# ATX80.net
KiCad netlist of a schematic drawn in EAGLE
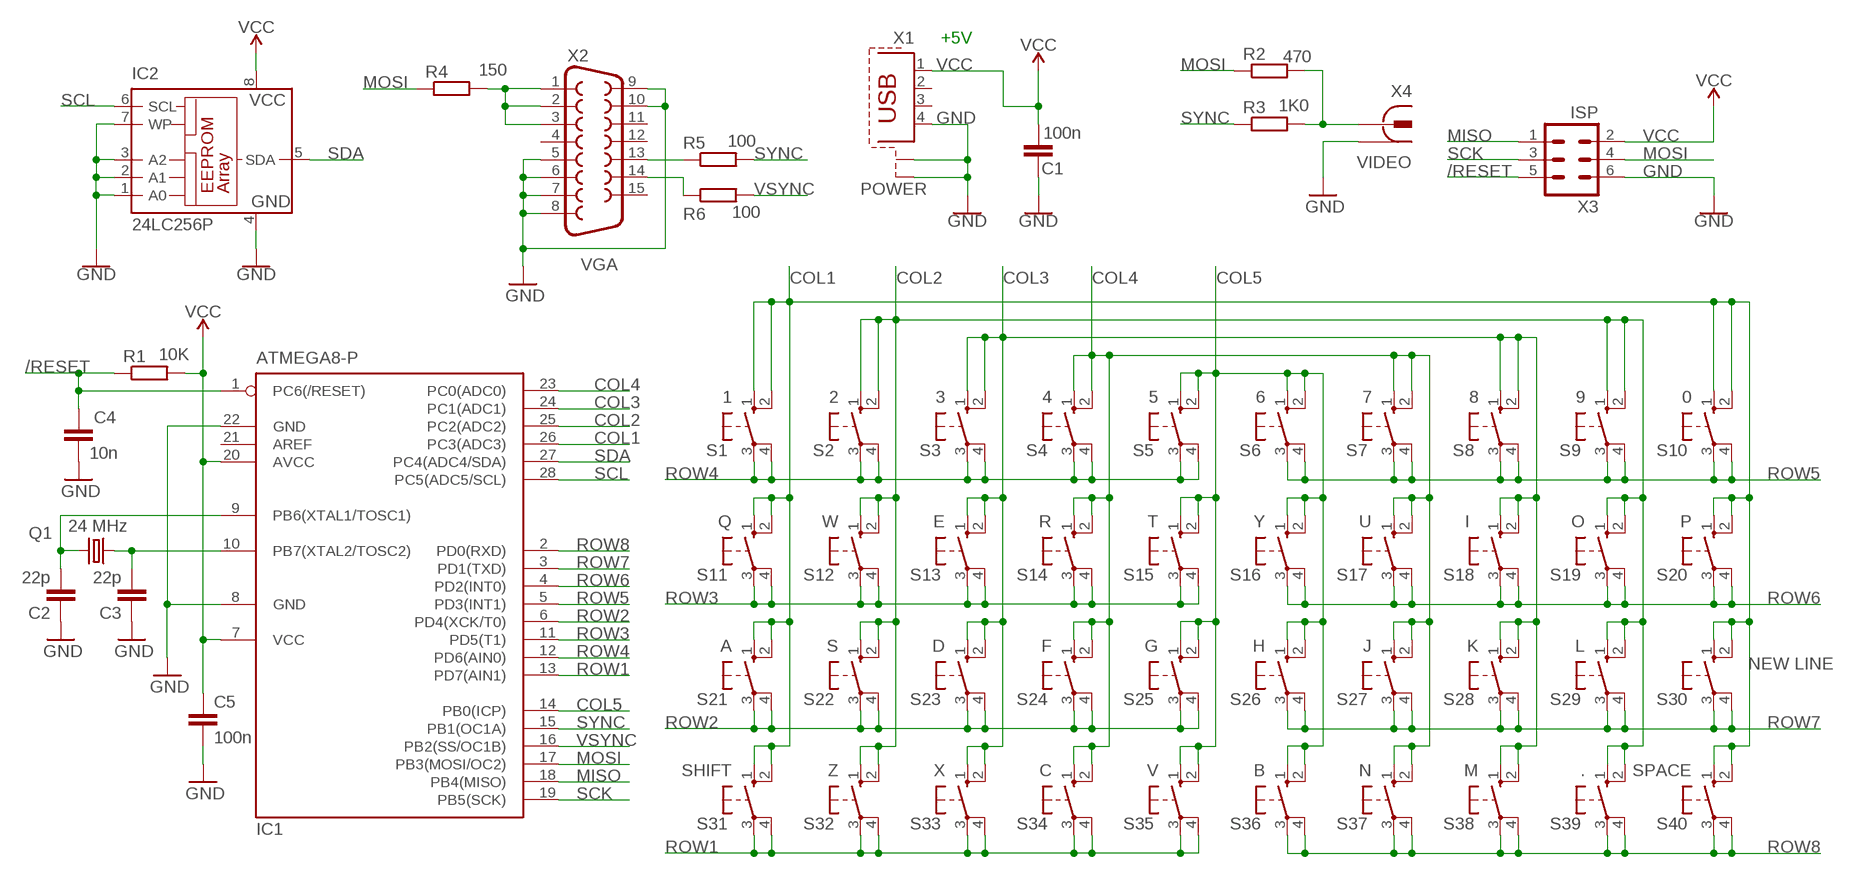
[diagram p0: schematic, sheet 1]

(export (version "E")
  (design (tool "Eeschema 10.0.6"))
  (components
    (comp (ref "C1")
      (value "100n")
      (footprint "eagle-import:C050-024X044")
      (libsource (lib "eagle-import") (part "C-EU050-024X044"))
    )
    (comp (ref "C2")
      (value "22p")
      (footprint "eagle-import:C050-024X044")
      (libsource (lib "eagle-import") (part "C-EU050-024X044"))
    )
    (comp (ref "C3")
      (value "22p")
      (footprint "eagle-import:C050-024X044")
      (libsource (lib "eagle-import") (part "C-EU050-024X044"))
    )
    (comp (ref "C4")
      (value "10n")
      (footprint "eagle-import:C050-024X044")
      (libsource (lib "eagle-import") (part "C-EU050-024X044"))
    )
    (comp (ref "C5")
      (value "100n")
      (footprint "eagle-import:C050-024X044")
      (libsource (lib "eagle-import") (part "C-EU050-024X044"))
    )
    (comp (ref "IC1")
      (value "ATMEGA8-P")
      (footprint "eagle-import:DIL28-3")
      (libsource (lib "eagle-import") (part "MEGA8-P"))
    )
    (comp (ref "IC2")
      (value "24LC256P")
      (footprint "eagle-import:DIL8")
      (fields (field (name "MF") "MICROCHIP") (field (name "MPN") "24LC256-E/P"))
      (libsource (lib "eagle-import") (part "24PLC256"))
    )
    (comp (ref "Q1")
      (value "24 MHz")
      (footprint "eagle-import:HC49U-V")
      (libsource (lib "eagle-import") (part "CRYSTALHC49U-V"))
    )
    (comp (ref "R1")
      (value "10K")
      (footprint "eagle-import:0204_7")
      (libsource (lib "eagle-import") (part "R-EU_0204/7"))
    )
    (comp (ref "R2")
      (value "470")
      (footprint "eagle-import:0204_7")
      (libsource (lib "eagle-import") (part "R-EU_0204/7"))
    )
    (comp (ref "R3")
      (value "1K0")
      (footprint "eagle-import:0204_7")
      (libsource (lib "eagle-import") (part "R-EU_0204/7"))
    )
    (comp (ref "R4")
      (value "150")
      (footprint "eagle-import:0204_7")
      (libsource (lib "eagle-import") (part "R-EU_0204/7"))
    )
    (comp (ref "R5")
      (value "100")
      (footprint "eagle-import:0204_7")
      (libsource (lib "eagle-import") (part "R-EU_0204/7"))
    )
    (comp (ref "R6")
      (value "100")
      (footprint "eagle-import:0204_7")
      (libsource (lib "eagle-import") (part "R-EU_0204/7"))
    )
    (comp (ref "S1")
      (value "1")
      (footprint "eagle-import:B3F-10XX")
      (fields (field (name "MPN") "B3F-1000"))
      (libsource (lib "eagle-import") (part "10-XX"))
    )
    (comp (ref "S2")
      (value "2")
      (footprint "eagle-import:B3F-10XX")
      (fields (field (name "MPN") "B3F-1000"))
      (libsource (lib "eagle-import") (part "10-XX"))
    )
    (comp (ref "S3")
      (value "3")
      (footprint "eagle-import:B3F-10XX")
      (fields (field (name "MPN") "B3F-1000"))
      (libsource (lib "eagle-import") (part "10-XX"))
    )
    (comp (ref "S4")
      (value "4")
      (footprint "eagle-import:B3F-10XX")
      (fields (field (name "MPN") "B3F-1000"))
      (libsource (lib "eagle-import") (part "10-XX"))
    )
    (comp (ref "S5")
      (value "5")
      (footprint "eagle-import:B3F-10XX")
      (fields (field (name "MPN") "B3F-1000"))
      (libsource (lib "eagle-import") (part "10-XX"))
    )
    (comp (ref "S6")
      (value "6")
      (footprint "eagle-import:B3F-10XX")
      (fields (field (name "MPN") "B3F-1000"))
      (libsource (lib "eagle-import") (part "10-XX"))
    )
    (comp (ref "S7")
      (value "7")
      (footprint "eagle-import:B3F-10XX")
      (fields (field (name "MPN") "B3F-1000"))
      (libsource (lib "eagle-import") (part "10-XX"))
    )
    (comp (ref "S8")
      (value "8")
      (footprint "eagle-import:B3F-10XX")
      (fields (field (name "MPN") "B3F-1000"))
      (libsource (lib "eagle-import") (part "10-XX"))
    )
    (comp (ref "S9")
      (value "9")
      (footprint "eagle-import:B3F-10XX")
      (fields (field (name "MPN") "B3F-1000"))
      (libsource (lib "eagle-import") (part "10-XX"))
    )
    (comp (ref "S10")
      (value "0")
      (footprint "eagle-import:B3F-10XX")
      (fields (field (name "MPN") "B3F-1000"))
      (libsource (lib "eagle-import") (part "10-XX"))
    )
    (comp (ref "S11")
      (value "Q")
      (footprint "eagle-import:B3F-10XX")
      (fields (field (name "MPN") "B3F-1000"))
      (libsource (lib "eagle-import") (part "10-XX"))
    )
    (comp (ref "S12")
      (value "W")
      (footprint "eagle-import:B3F-10XX")
      (fields (field (name "MPN") "B3F-1000"))
      (libsource (lib "eagle-import") (part "10-XX"))
    )
    (comp (ref "S13")
      (value "E")
      (footprint "eagle-import:B3F-10XX")
      (fields (field (name "MPN") "B3F-1000"))
      (libsource (lib "eagle-import") (part "10-XX"))
    )
    (comp (ref "S14")
      (value "R")
      (footprint "eagle-import:B3F-10XX")
      (fields (field (name "MPN") "B3F-1000"))
      (libsource (lib "eagle-import") (part "10-XX"))
    )
    (comp (ref "S15")
      (value "T")
      (footprint "eagle-import:B3F-10XX")
      (fields (field (name "MPN") "B3F-1000"))
      (libsource (lib "eagle-import") (part "10-XX"))
    )
    (comp (ref "S16")
      (value "Y")
      (footprint "eagle-import:B3F-10XX")
      (fields (field (name "MPN") "B3F-1000"))
      (libsource (lib "eagle-import") (part "10-XX"))
    )
    (comp (ref "S17")
      (value "U")
      (footprint "eagle-import:B3F-10XX")
      (fields (field (name "MPN") "B3F-1000"))
      (libsource (lib "eagle-import") (part "10-XX"))
    )
    (comp (ref "S18")
      (value "I")
      (footprint "eagle-import:B3F-10XX")
      (fields (field (name "MPN") "B3F-1000"))
      (libsource (lib "eagle-import") (part "10-XX"))
    )
    (comp (ref "S19")
      (value "O")
      (footprint "eagle-import:B3F-10XX")
      (fields (field (name "MPN") "B3F-1000"))
      (libsource (lib "eagle-import") (part "10-XX"))
    )
    (comp (ref "S20")
      (value "P")
      (footprint "eagle-import:B3F-10XX")
      (fields (field (name "MPN") "B3F-1000"))
      (libsource (lib "eagle-import") (part "10-XX"))
    )
    (comp (ref "S21")
      (value "A")
      (footprint "eagle-import:B3F-10XX")
      (fields (field (name "MPN") "B3F-1000"))
      (libsource (lib "eagle-import") (part "10-XX"))
    )
    (comp (ref "S22")
      (value "S")
      (footprint "eagle-import:B3F-10XX")
      (fields (field (name "MPN") "B3F-1000"))
      (libsource (lib "eagle-import") (part "10-XX"))
    )
    (comp (ref "S23")
      (value "D")
      (footprint "eagle-import:B3F-10XX")
      (fields (field (name "MPN") "B3F-1000"))
      (libsource (lib "eagle-import") (part "10-XX"))
    )
    (comp (ref "S24")
      (value "F")
      (footprint "eagle-import:B3F-10XX")
      (fields (field (name "MPN") "B3F-1000"))
      (libsource (lib "eagle-import") (part "10-XX"))
    )
    (comp (ref "S25")
      (value "G")
      (footprint "eagle-import:B3F-10XX")
      (fields (field (name "MPN") "B3F-1000"))
      (libsource (lib "eagle-import") (part "10-XX"))
    )
    (comp (ref "S26")
      (value "H")
      (footprint "eagle-import:B3F-10XX")
      (fields (field (name "MPN") "B3F-1000"))
      (libsource (lib "eagle-import") (part "10-XX"))
    )
    (comp (ref "S27")
      (value "J")
      (footprint "eagle-import:B3F-10XX")
      (fields (field (name "MPN") "B3F-1000"))
      (libsource (lib "eagle-import") (part "10-XX"))
    )
    (comp (ref "S28")
      (value "K")
      (footprint "eagle-import:B3F-10XX")
      (fields (field (name "MPN") "B3F-1000"))
      (libsource (lib "eagle-import") (part "10-XX"))
    )
    (comp (ref "S29")
      (value "L")
      (footprint "eagle-import:B3F-10XX")
      (fields (field (name "MPN") "B3F-1000"))
      (libsource (lib "eagle-import") (part "10-XX"))
    )
    (comp (ref "S30")
      (value "NEW LINE")
      (footprint "eagle-import:B3F-10XX")
      (fields (field (name "MPN") "B3F-1000"))
      (libsource (lib "eagle-import") (part "10-XX"))
    )
    (comp (ref "S31")
      (value "SHIFT")
      (footprint "eagle-import:B3F-10XX")
      (fields (field (name "MPN") "B3F-1000"))
      (libsource (lib "eagle-import") (part "10-XX"))
    )
    (comp (ref "S32")
      (value "Z")
      (footprint "eagle-import:B3F-10XX")
      (fields (field (name "MPN") "B3F-1000"))
      (libsource (lib "eagle-import") (part "10-XX"))
    )
    (comp (ref "S33")
      (value "X")
      (footprint "eagle-import:B3F-10XX")
      (fields (field (name "MPN") "B3F-1000"))
      (libsource (lib "eagle-import") (part "10-XX"))
    )
    (comp (ref "S34")
      (value "C")
      (footprint "eagle-import:B3F-10XX")
      (fields (field (name "MPN") "B3F-1000"))
      (libsource (lib "eagle-import") (part "10-XX"))
    )
    (comp (ref "S35")
      (value "V")
      (footprint "eagle-import:B3F-10XX")
      (fields (field (name "MPN") "B3F-1000"))
      (libsource (lib "eagle-import") (part "10-XX"))
    )
    (comp (ref "S36")
      (value "B")
      (footprint "eagle-import:B3F-10XX")
      (fields (field (name "MPN") "B3F-1000"))
      (libsource (lib "eagle-import") (part "10-XX"))
    )
    (comp (ref "S37")
      (value "N")
      (footprint "eagle-import:B3F-10XX")
      (fields (field (name "MPN") "B3F-1000"))
      (libsource (lib "eagle-import") (part "10-XX"))
    )
    (comp (ref "S38")
      (value "M")
      (footprint "eagle-import:B3F-10XX")
      (fields (field (name "MPN") "B3F-1000"))
      (libsource (lib "eagle-import") (part "10-XX"))
    )
    (comp (ref "S39")
      (value ".")
      (footprint "eagle-import:B3F-10XX")
      (fields (field (name "MPN") "B3F-1000"))
      (libsource (lib "eagle-import") (part "10-XX"))
    )
    (comp (ref "S40")
      (value "SPACE")
      (footprint "eagle-import:B3F-10XX")
      (fields (field (name "MPN") "B3F-1000"))
      (libsource (lib "eagle-import") (part "10-XX"))
    )
    (comp (ref "X1")
      (value "POWER")
      (footprint "eagle-import:PN61729-S")
      (libsource (lib "eagle-import") (part "PN61729-S"))
    )
    (comp (ref "X2")
      (value "VGA")
      (footprint "eagle-import:HDF15H")
      (libsource (lib "eagle-import") (part "F15HDH"))
    )
    (comp (ref "X3")
      (value "ISP")
      (footprint "eagle-import:ML6L")
      (libsource (lib "eagle-import") (part "ML6L"))
    )
    (comp (ref "X4")
      (value "VIDEO")
      (footprint "eagle-import:736880-49")
      (libsource (lib "eagle-import") (part "736880-49"))
    )
  )
  (nets
    (net (code "1") (name "/COL1") (class "Default")
      (node (ref "IC1") (pin "26") (pinfunction "PC3(ADC3)_26") (pintype "bidirectional"))
      (node (ref "S1") (pin "1") (pinfunction "S_1") (pintype "passive"))
      (node (ref "S1") (pin "2") (pinfunction "S1_2") (pintype "passive"))
      (node (ref "S10") (pin "1") (pinfunction "S_1") (pintype "passive"))
      (node (ref "S10") (pin "2") (pinfunction "S1_2") (pintype "passive"))
      (node (ref "S11") (pin "1") (pinfunction "S_1") (pintype "passive"))
      (node (ref "S11") (pin "2") (pinfunction "S1_2") (pintype "passive"))
      (node (ref "S20") (pin "1") (pinfunction "S_1") (pintype "passive"))
      (node (ref "S20") (pin "2") (pinfunction "S1_2") (pintype "passive"))
      (node (ref "S21") (pin "1") (pinfunction "S_1") (pintype "passive"))
      (node (ref "S21") (pin "2") (pinfunction "S1_2") (pintype "passive"))
      (node (ref "S30") (pin "1") (pinfunction "S_1") (pintype "passive"))
      (node (ref "S30") (pin "2") (pinfunction "S1_2") (pintype "passive"))
      (node (ref "S31") (pin "1") (pinfunction "S_1") (pintype "passive"))
      (node (ref "S31") (pin "2") (pinfunction "S1_2") (pintype "passive"))
      (node (ref "S40") (pin "1") (pinfunction "S_1") (pintype "passive"))
      (node (ref "S40") (pin "2") (pinfunction "S1_2") (pintype "passive"))
    )
    (net (code "2") (name "/COL2") (class "Default")
      (node (ref "IC1") (pin "25") (pinfunction "PC2(ADC2)_25") (pintype "bidirectional"))
      (node (ref "S12") (pin "1") (pinfunction "S_1") (pintype "passive"))
      (node (ref "S12") (pin "2") (pinfunction "S1_2") (pintype "passive"))
      (node (ref "S19") (pin "1") (pinfunction "S_1") (pintype "passive"))
      (node (ref "S19") (pin "2") (pinfunction "S1_2") (pintype "passive"))
      (node (ref "S2") (pin "1") (pinfunction "S_1") (pintype "passive"))
      (node (ref "S2") (pin "2") (pinfunction "S1_2") (pintype "passive"))
      (node (ref "S22") (pin "1") (pinfunction "S_1") (pintype "passive"))
      (node (ref "S22") (pin "2") (pinfunction "S1_2") (pintype "passive"))
      (node (ref "S29") (pin "1") (pinfunction "S_1") (pintype "passive"))
      (node (ref "S29") (pin "2") (pinfunction "S1_2") (pintype "passive"))
      (node (ref "S32") (pin "1") (pinfunction "S_1") (pintype "passive"))
      (node (ref "S32") (pin "2") (pinfunction "S1_2") (pintype "passive"))
      (node (ref "S39") (pin "1") (pinfunction "S_1") (pintype "passive"))
      (node (ref "S39") (pin "2") (pinfunction "S1_2") (pintype "passive"))
      (node (ref "S9") (pin "1") (pinfunction "S_1") (pintype "passive"))
      (node (ref "S9") (pin "2") (pinfunction "S1_2") (pintype "passive"))
    )
    (net (code "3") (name "/COL3") (class "Default")
      (node (ref "IC1") (pin "24") (pinfunction "PC1(ADC1)_24") (pintype "bidirectional"))
      (node (ref "S13") (pin "1") (pinfunction "S_1") (pintype "passive"))
      (node (ref "S13") (pin "2") (pinfunction "S1_2") (pintype "passive"))
      (node (ref "S18") (pin "1") (pinfunction "S_1") (pintype "passive"))
      (node (ref "S18") (pin "2") (pinfunction "S1_2") (pintype "passive"))
      (node (ref "S23") (pin "1") (pinfunction "S_1") (pintype "passive"))
      (node (ref "S23") (pin "2") (pinfunction "S1_2") (pintype "passive"))
      (node (ref "S28") (pin "1") (pinfunction "S_1") (pintype "passive"))
      (node (ref "S28") (pin "2") (pinfunction "S1_2") (pintype "passive"))
      (node (ref "S3") (pin "1") (pinfunction "S_1") (pintype "passive"))
      (node (ref "S3") (pin "2") (pinfunction "S1_2") (pintype "passive"))
      (node (ref "S33") (pin "1") (pinfunction "S_1") (pintype "passive"))
      (node (ref "S33") (pin "2") (pinfunction "S1_2") (pintype "passive"))
      (node (ref "S38") (pin "1") (pinfunction "S_1") (pintype "passive"))
      (node (ref "S38") (pin "2") (pinfunction "S1_2") (pintype "passive"))
      (node (ref "S8") (pin "1") (pinfunction "S_1") (pintype "passive"))
      (node (ref "S8") (pin "2") (pinfunction "S1_2") (pintype "passive"))
    )
    (net (code "4") (name "/COL4") (class "Default")
      (node (ref "IC1") (pin "23") (pinfunction "PC0(ADC0)_23") (pintype "bidirectional"))
      (node (ref "S14") (pin "1") (pinfunction "S_1") (pintype "passive"))
      (node (ref "S14") (pin "2") (pinfunction "S1_2") (pintype "passive"))
      (node (ref "S17") (pin "1") (pinfunction "S_1") (pintype "passive"))
      (node (ref "S17") (pin "2") (pinfunction "S1_2") (pintype "passive"))
      (node (ref "S24") (pin "1") (pinfunction "S_1") (pintype "passive"))
      (node (ref "S24") (pin "2") (pinfunction "S1_2") (pintype "passive"))
      (node (ref "S27") (pin "1") (pinfunction "S_1") (pintype "passive"))
      (node (ref "S27") (pin "2") (pinfunction "S1_2") (pintype "passive"))
      (node (ref "S34") (pin "1") (pinfunction "S_1") (pintype "passive"))
      (node (ref "S34") (pin "2") (pinfunction "S1_2") (pintype "passive"))
      (node (ref "S37") (pin "1") (pinfunction "S_1") (pintype "passive"))
      (node (ref "S37") (pin "2") (pinfunction "S1_2") (pintype "passive"))
      (node (ref "S4") (pin "1") (pinfunction "S_1") (pintype "passive"))
      (node (ref "S4") (pin "2") (pinfunction "S1_2") (pintype "passive"))
      (node (ref "S7") (pin "1") (pinfunction "S_1") (pintype "passive"))
      (node (ref "S7") (pin "2") (pinfunction "S1_2") (pintype "passive"))
    )
    (net (code "5") (name "/COL5") (class "Default")
      (node (ref "IC1") (pin "14") (pinfunction "PB0(ICP)_14") (pintype "bidirectional"))
      (node (ref "S15") (pin "1") (pinfunction "S_1") (pintype "passive"))
      (node (ref "S15") (pin "2") (pinfunction "S1_2") (pintype "passive"))
      (node (ref "S16") (pin "1") (pinfunction "S_1") (pintype "passive"))
      (node (ref "S16") (pin "2") (pinfunction "S1_2") (pintype "passive"))
      (node (ref "S25") (pin "1") (pinfunction "S_1") (pintype "passive"))
      (node (ref "S25") (pin "2") (pinfunction "S1_2") (pintype "passive"))
      (node (ref "S26") (pin "1") (pinfunction "S_1") (pintype "passive"))
      (node (ref "S26") (pin "2") (pinfunction "S1_2") (pintype "passive"))
      (node (ref "S35") (pin "1") (pinfunction "S_1") (pintype "passive"))
      (node (ref "S35") (pin "2") (pinfunction "S1_2") (pintype "passive"))
      (node (ref "S36") (pin "1") (pinfunction "S_1") (pintype "passive"))
      (node (ref "S36") (pin "2") (pinfunction "S1_2") (pintype "passive"))
      (node (ref "S5") (pin "1") (pinfunction "S_1") (pintype "passive"))
      (node (ref "S5") (pin "2") (pinfunction "S1_2") (pintype "passive"))
      (node (ref "S6") (pin "1") (pinfunction "S_1") (pintype "passive"))
      (node (ref "S6") (pin "2") (pinfunction "S1_2") (pintype "passive"))
    )
    (net (code "6") (name "/MISO") (class "Default")
      (node (ref "IC1") (pin "18") (pinfunction "PB4(MISO)_18") (pintype "bidirectional"))
      (node (ref "X3") (pin "1") (pinfunction "1_1") (pintype "passive"))
    )
    (net (code "7") (name "/MOSI") (class "Default")
      (node (ref "IC1") (pin "17") (pinfunction "PB3(MOSI/OC2)_17") (pintype "bidirectional"))
      (node (ref "R2") (pin "1") (pinfunction "1_1") (pintype "passive"))
      (node (ref "R4") (pin "1") (pinfunction "1_1") (pintype "passive"))
      (node (ref "X3") (pin "4") (pinfunction "4_4") (pintype "passive"))
    )
    (net (code "8") (name "/ROW1") (class "Default")
      (node (ref "IC1") (pin "13") (pinfunction "PD7(AIN1)_13") (pintype "bidirectional"))
      (node (ref "S31") (pin "3") (pinfunction "P_3") (pintype "passive"))
      (node (ref "S31") (pin "4") (pinfunction "P1_4") (pintype "passive"))
      (node (ref "S32") (pin "3") (pinfunction "P_3") (pintype "passive"))
      (node (ref "S32") (pin "4") (pinfunction "P1_4") (pintype "passive"))
      (node (ref "S33") (pin "3") (pinfunction "P_3") (pintype "passive"))
      (node (ref "S33") (pin "4") (pinfunction "P1_4") (pintype "passive"))
      (node (ref "S34") (pin "3") (pinfunction "P_3") (pintype "passive"))
      (node (ref "S34") (pin "4") (pinfunction "P1_4") (pintype "passive"))
      (node (ref "S35") (pin "3") (pinfunction "P_3") (pintype "passive"))
      (node (ref "S35") (pin "4") (pinfunction "P1_4") (pintype "passive"))
    )
    (net (code "9") (name "/ROW2") (class "Default")
      (node (ref "IC1") (pin "6") (pinfunction "PD4(XCK/T0)_6") (pintype "bidirectional"))
      (node (ref "S21") (pin "3") (pinfunction "P_3") (pintype "passive"))
      (node (ref "S21") (pin "4") (pinfunction "P1_4") (pintype "passive"))
      (node (ref "S22") (pin "3") (pinfunction "P_3") (pintype "passive"))
      (node (ref "S22") (pin "4") (pinfunction "P1_4") (pintype "passive"))
      (node (ref "S23") (pin "3") (pinfunction "P_3") (pintype "passive"))
      (node (ref "S23") (pin "4") (pinfunction "P1_4") (pintype "passive"))
      (node (ref "S24") (pin "3") (pinfunction "P_3") (pintype "passive"))
      (node (ref "S24") (pin "4") (pinfunction "P1_4") (pintype "passive"))
      (node (ref "S25") (pin "3") (pinfunction "P_3") (pintype "passive"))
      (node (ref "S25") (pin "4") (pinfunction "P1_4") (pintype "passive"))
    )
    (net (code "10") (name "/ROW3") (class "Default")
      (node (ref "IC1") (pin "11") (pinfunction "PD5(T1)_11") (pintype "bidirectional"))
      (node (ref "S11") (pin "3") (pinfunction "P_3") (pintype "passive"))
      (node (ref "S11") (pin "4") (pinfunction "P1_4") (pintype "passive"))
      (node (ref "S12") (pin "3") (pinfunction "P_3") (pintype "passive"))
      (node (ref "S12") (pin "4") (pinfunction "P1_4") (pintype "passive"))
      (node (ref "S13") (pin "3") (pinfunction "P_3") (pintype "passive"))
      (node (ref "S13") (pin "4") (pinfunction "P1_4") (pintype "passive"))
      (node (ref "S14") (pin "3") (pinfunction "P_3") (pintype "passive"))
      (node (ref "S14") (pin "4") (pinfunction "P1_4") (pintype "passive"))
      (node (ref "S15") (pin "3") (pinfunction "P_3") (pintype "passive"))
      (node (ref "S15") (pin "4") (pinfunction "P1_4") (pintype "passive"))
    )
    (net (code "11") (name "/ROW4") (class "Default")
      (node (ref "IC1") (pin "12") (pinfunction "PD6(AIN0)_12") (pintype "bidirectional"))
      (node (ref "S1") (pin "3") (pinfunction "P_3") (pintype "passive"))
      (node (ref "S1") (pin "4") (pinfunction "P1_4") (pintype "passive"))
      (node (ref "S2") (pin "3") (pinfunction "P_3") (pintype "passive"))
      (node (ref "S2") (pin "4") (pinfunction "P1_4") (pintype "passive"))
      (node (ref "S3") (pin "3") (pinfunction "P_3") (pintype "passive"))
      (node (ref "S3") (pin "4") (pinfunction "P1_4") (pintype "passive"))
      (node (ref "S4") (pin "3") (pinfunction "P_3") (pintype "passive"))
      (node (ref "S4") (pin "4") (pinfunction "P1_4") (pintype "passive"))
      (node (ref "S5") (pin "3") (pinfunction "P_3") (pintype "passive"))
      (node (ref "S5") (pin "4") (pinfunction "P1_4") (pintype "passive"))
    )
    (net (code "12") (name "/ROW5") (class "Default")
      (node (ref "IC1") (pin "5") (pinfunction "PD3(INT1)_5") (pintype "bidirectional"))
      (node (ref "S10") (pin "3") (pinfunction "P_3") (pintype "passive"))
      (node (ref "S10") (pin "4") (pinfunction "P1_4") (pintype "passive"))
      (node (ref "S6") (pin "3") (pinfunction "P_3") (pintype "passive"))
      (node (ref "S6") (pin "4") (pinfunction "P1_4") (pintype "passive"))
      (node (ref "S7") (pin "3") (pinfunction "P_3") (pintype "passive"))
      (node (ref "S7") (pin "4") (pinfunction "P1_4") (pintype "passive"))
      (node (ref "S8") (pin "3") (pinfunction "P_3") (pintype "passive"))
      (node (ref "S8") (pin "4") (pinfunction "P1_4") (pintype "passive"))
      (node (ref "S9") (pin "3") (pinfunction "P_3") (pintype "passive"))
      (node (ref "S9") (pin "4") (pinfunction "P1_4") (pintype "passive"))
    )
    (net (code "13") (name "/ROW6") (class "Default")
      (node (ref "IC1") (pin "4") (pinfunction "PD2(INT0)_4") (pintype "bidirectional"))
      (node (ref "S16") (pin "3") (pinfunction "P_3") (pintype "passive"))
      (node (ref "S16") (pin "4") (pinfunction "P1_4") (pintype "passive"))
      (node (ref "S17") (pin "3") (pinfunction "P_3") (pintype "passive"))
      (node (ref "S17") (pin "4") (pinfunction "P1_4") (pintype "passive"))
      (node (ref "S18") (pin "3") (pinfunction "P_3") (pintype "passive"))
      (node (ref "S18") (pin "4") (pinfunction "P1_4") (pintype "passive"))
      (node (ref "S19") (pin "3") (pinfunction "P_3") (pintype "passive"))
      (node (ref "S19") (pin "4") (pinfunction "P1_4") (pintype "passive"))
      (node (ref "S20") (pin "3") (pinfunction "P_3") (pintype "passive"))
      (node (ref "S20") (pin "4") (pinfunction "P1_4") (pintype "passive"))
    )
    (net (code "14") (name "/ROW7") (class "Default")
      (node (ref "IC1") (pin "3") (pinfunction "PD1(TXD)_3") (pintype "bidirectional"))
      (node (ref "S26") (pin "3") (pinfunction "P_3") (pintype "passive"))
      (node (ref "S26") (pin "4") (pinfunction "P1_4") (pintype "passive"))
      (node (ref "S27") (pin "3") (pinfunction "P_3") (pintype "passive"))
      (node (ref "S27") (pin "4") (pinfunction "P1_4") (pintype "passive"))
      (node (ref "S28") (pin "3") (pinfunction "P_3") (pintype "passive"))
      (node (ref "S28") (pin "4") (pinfunction "P1_4") (pintype "passive"))
      (node (ref "S29") (pin "3") (pinfunction "P_3") (pintype "passive"))
      (node (ref "S29") (pin "4") (pinfunction "P1_4") (pintype "passive"))
      (node (ref "S30") (pin "3") (pinfunction "P_3") (pintype "passive"))
      (node (ref "S30") (pin "4") (pinfunction "P1_4") (pintype "passive"))
    )
    (net (code "15") (name "/ROW8") (class "Default")
      (node (ref "IC1") (pin "2") (pinfunction "PD0(RXD)_2") (pintype "bidirectional"))
      (node (ref "S36") (pin "3") (pinfunction "P_3") (pintype "passive"))
      (node (ref "S36") (pin "4") (pinfunction "P1_4") (pintype "passive"))
      (node (ref "S37") (pin "3") (pinfunction "P_3") (pintype "passive"))
      (node (ref "S37") (pin "4") (pinfunction "P1_4") (pintype "passive"))
      (node (ref "S38") (pin "3") (pinfunction "P_3") (pintype "passive"))
      (node (ref "S38") (pin "4") (pinfunction "P1_4") (pintype "passive"))
      (node (ref "S39") (pin "3") (pinfunction "P_3") (pintype "passive"))
      (node (ref "S39") (pin "4") (pinfunction "P1_4") (pintype "passive"))
      (node (ref "S40") (pin "3") (pinfunction "P_3") (pintype "passive"))
      (node (ref "S40") (pin "4") (pinfunction "P1_4") (pintype "passive"))
    )
    (net (code "16") (name "/SCK") (class "Default")
      (node (ref "IC1") (pin "19") (pinfunction "PB5(SCK)_19") (pintype "bidirectional"))
      (node (ref "X3") (pin "3") (pinfunction "3_3") (pintype "passive"))
    )
    (net (code "17") (name "/SCL") (class "Default")
      (node (ref "IC1") (pin "28") (pinfunction "PC5(ADC5/SCL)_28") (pintype "bidirectional"))
      (node (ref "IC2") (pin "6") (pinfunction "SCL_6") (pintype "input"))
    )
    (net (code "18") (name "/SDA") (class "Default")
      (node (ref "IC1") (pin "27") (pinfunction "PC4(ADC4/SDA)_27") (pintype "bidirectional"))
      (node (ref "IC2") (pin "5") (pinfunction "SDA_5") (pintype "bidirectional"))
    )
    (net (code "19") (name "/SYNC") (class "Default")
      (node (ref "IC1") (pin "15") (pinfunction "PB1(OC1A)_15") (pintype "bidirectional"))
      (node (ref "R3") (pin "1") (pinfunction "1_1") (pintype "passive"))
      (node (ref "R5") (pin "2") (pinfunction "2_2") (pintype "passive"))
    )
    (net (code "20") (name "/VSYNC") (class "Default")
      (node (ref "IC1") (pin "16") (pinfunction "PB2(SS/OC1B)_16") (pintype "bidirectional"))
      (node (ref "R6") (pin "2") (pinfunction "2_2") (pintype "passive"))
    )
    (net (code "21") (name "/{slash}RESET") (class "Default")
      (node (ref "C4") (pin "1") (pinfunction "1_1") (pintype "passive"))
      (node (ref "IC1") (pin "1") (pinfunction "PC6(/RESET)_1") (pintype "bidirectional"))
      (node (ref "R1") (pin "1") (pinfunction "1_1") (pintype "passive"))
      (node (ref "X3") (pin "5") (pinfunction "5_5") (pintype "passive"))
    )
    (net (code "22") (name "GND") (class "Default")
      (node (ref "C1") (pin "1") (pinfunction "1_1") (pintype "passive"))
      (node (ref "C2") (pin "1") (pinfunction "1_1") (pintype "passive"))
      (node (ref "C3") (pin "1") (pinfunction "1_1") (pintype "passive"))
      (node (ref "C4") (pin "2") (pinfunction "2_2") (pintype "passive"))
      (node (ref "C5") (pin "2") (pinfunction "2_2") (pintype "passive"))
      (node (ref "IC1") (pin "22") (pinfunction "GND_22") (pintype "power_in"))
      (node (ref "IC1") (pin "8") (pinfunction "GND_8") (pintype "power_in"))
      (node (ref "IC2") (pin "1") (pinfunction "A0_1") (pintype "input"))
      (node (ref "IC2") (pin "2") (pinfunction "A1_2") (pintype "input"))
      (node (ref "IC2") (pin "3") (pinfunction "A2_3") (pintype "input"))
      (node (ref "IC2") (pin "4") (pinfunction "GND_4") (pintype "power_in"))
      (node (ref "IC2") (pin "7") (pinfunction "WP_7") (pintype "input"))
      (node (ref "X1") (pin "4") (pinfunction "4_4") (pintype "passive"))
      (node (ref "X1") (pin "S1") (pinfunction "S1_S1") (pintype "passive"))
      (node (ref "X1") (pin "S2") (pinfunction "S2_S2") (pintype "passive"))
      (node (ref "X2") (pin "10") (pinfunction "10_10") (pintype "passive"))
      (node (ref "X2") (pin "5") (pinfunction "5_5") (pintype "passive"))
      (node (ref "X2") (pin "6") (pinfunction "6_6") (pintype "passive"))
      (node (ref "X2") (pin "7") (pinfunction "7_7") (pintype "passive"))
      (node (ref "X2") (pin "8") (pinfunction "8_8") (pintype "passive"))
      (node (ref "X2") (pin "9") (pinfunction "9_9") (pintype "passive"))
      (node (ref "X3") (pin "6") (pinfunction "6_6") (pintype "passive"))
      (node (ref "X4") (pin "1") (pinfunction "1_1") (pintype "passive"))
      (node (ref "X4") (pin "1@1") (pinfunction "1_1@1") (pintype "passive"))
      (node (ref "X4") (pin "1@2") (pinfunction "1_1@2") (pintype "passive"))
    )
    (net (code "23") (name "Net-(IC1-PB6(XTAL1{slash}TOSC1))") (class "Default")
      (node (ref "C2") (pin "2") (pinfunction "2_2") (pintype "passive"))
      (node (ref "IC1") (pin "9") (pinfunction "PB6(XTAL1/TOSC1)_9") (pintype "bidirectional"))
      (node (ref "Q1") (pin "2") (pinfunction "2_2") (pintype "passive"))
    )
    (net (code "24") (name "Net-(IC1-PB7(XTAL2{slash}TOSC2))") (class "Default")
      (node (ref "C3") (pin "2") (pinfunction "2_2") (pintype "passive"))
      (node (ref "IC1") (pin "10") (pinfunction "PB7(XTAL2/TOSC2)_10") (pintype "bidirectional"))
      (node (ref "Q1") (pin "1") (pinfunction "1_1") (pintype "passive"))
    )
    (net (code "25") (name "Net-(R2-Pad2)") (class "Default")
      (node (ref "R2") (pin "2") (pinfunction "2_2") (pintype "passive"))
      (node (ref "R3") (pin "2") (pinfunction "2_2") (pintype "passive"))
      (node (ref "X4") (pin "2") (pinfunction "2_2") (pintype "passive"))
    )
    (net (code "26") (name "Net-(R4-Pad2)") (class "Default")
      (node (ref "R4") (pin "2") (pinfunction "2_2") (pintype "passive"))
      (node (ref "X2") (pin "1") (pinfunction "1_1") (pintype "passive"))
      (node (ref "X2") (pin "2") (pinfunction "2_2") (pintype "passive"))
      (node (ref "X2") (pin "3") (pinfunction "3_3") (pintype "passive"))
    )
    (net (code "27") (name "Net-(R5-Pad1)") (class "Default")
      (node (ref "R5") (pin "1") (pinfunction "1_1") (pintype "passive"))
      (node (ref "X2") (pin "13") (pinfunction "13_13") (pintype "passive"))
    )
    (net (code "28") (name "Net-(R6-Pad1)") (class "Default")
      (node (ref "R6") (pin "1") (pinfunction "1_1") (pintype "passive"))
      (node (ref "X2") (pin "14") (pinfunction "14_14") (pintype "passive"))
    )
    (net (code "29") (name "VCC") (class "Default")
      (node (ref "C1") (pin "2") (pinfunction "2_2") (pintype "passive"))
      (node (ref "C5") (pin "1") (pinfunction "1_1") (pintype "passive"))
      (node (ref "IC1") (pin "20") (pinfunction "AVCC_20") (pintype "power_in"))
      (node (ref "IC1") (pin "7") (pinfunction "VCC_7") (pintype "power_in"))
      (node (ref "IC2") (pin "8") (pinfunction "VCC_8") (pintype "power_in"))
      (node (ref "R1") (pin "2") (pinfunction "2_2") (pintype "passive"))
      (node (ref "X1") (pin "1") (pinfunction "1_1") (pintype "passive"))
      (node (ref "X3") (pin "2") (pinfunction "2_2") (pintype "passive"))
    )
    (net (code "30") (name "unconnected-(IC1-AREF-Pad21)") (class "Default")
      (node (ref "IC1") (pin "21") (pinfunction "AREF_21") (pintype "passive"))
    )
    (net (code "31") (name "unconnected-(X1-Pad2)") (class "Default")
      (node (ref "X1") (pin "2") (pinfunction "2_2") (pintype "passive"))
    )
    (net (code "32") (name "unconnected-(X1-Pad3)") (class "Default")
      (node (ref "X1") (pin "3") (pinfunction "3_3") (pintype "passive"))
    )
    (net (code "33") (name "unconnected-(X2-Pad4)") (class "Default")
      (node (ref "X2") (pin "4") (pinfunction "4_4") (pintype "passive"))
    )
    (net (code "34") (name "unconnected-(X2-Pad11)") (class "Default")
      (node (ref "X2") (pin "11") (pinfunction "11_11") (pintype "passive"))
    )
    (net (code "35") (name "unconnected-(X2-Pad12)") (class "Default")
      (node (ref "X2") (pin "12") (pinfunction "12_12") (pintype "passive"))
    )
    (net (code "36") (name "unconnected-(X2-Pad15)") (class "Default")
      (node (ref "X2") (pin "15") (pinfunction "15_15") (pintype "passive"))
    )
  )
)
